# USBControlledAudioMixer.net
KiCad netlist of a schematic drawn in EAGLE
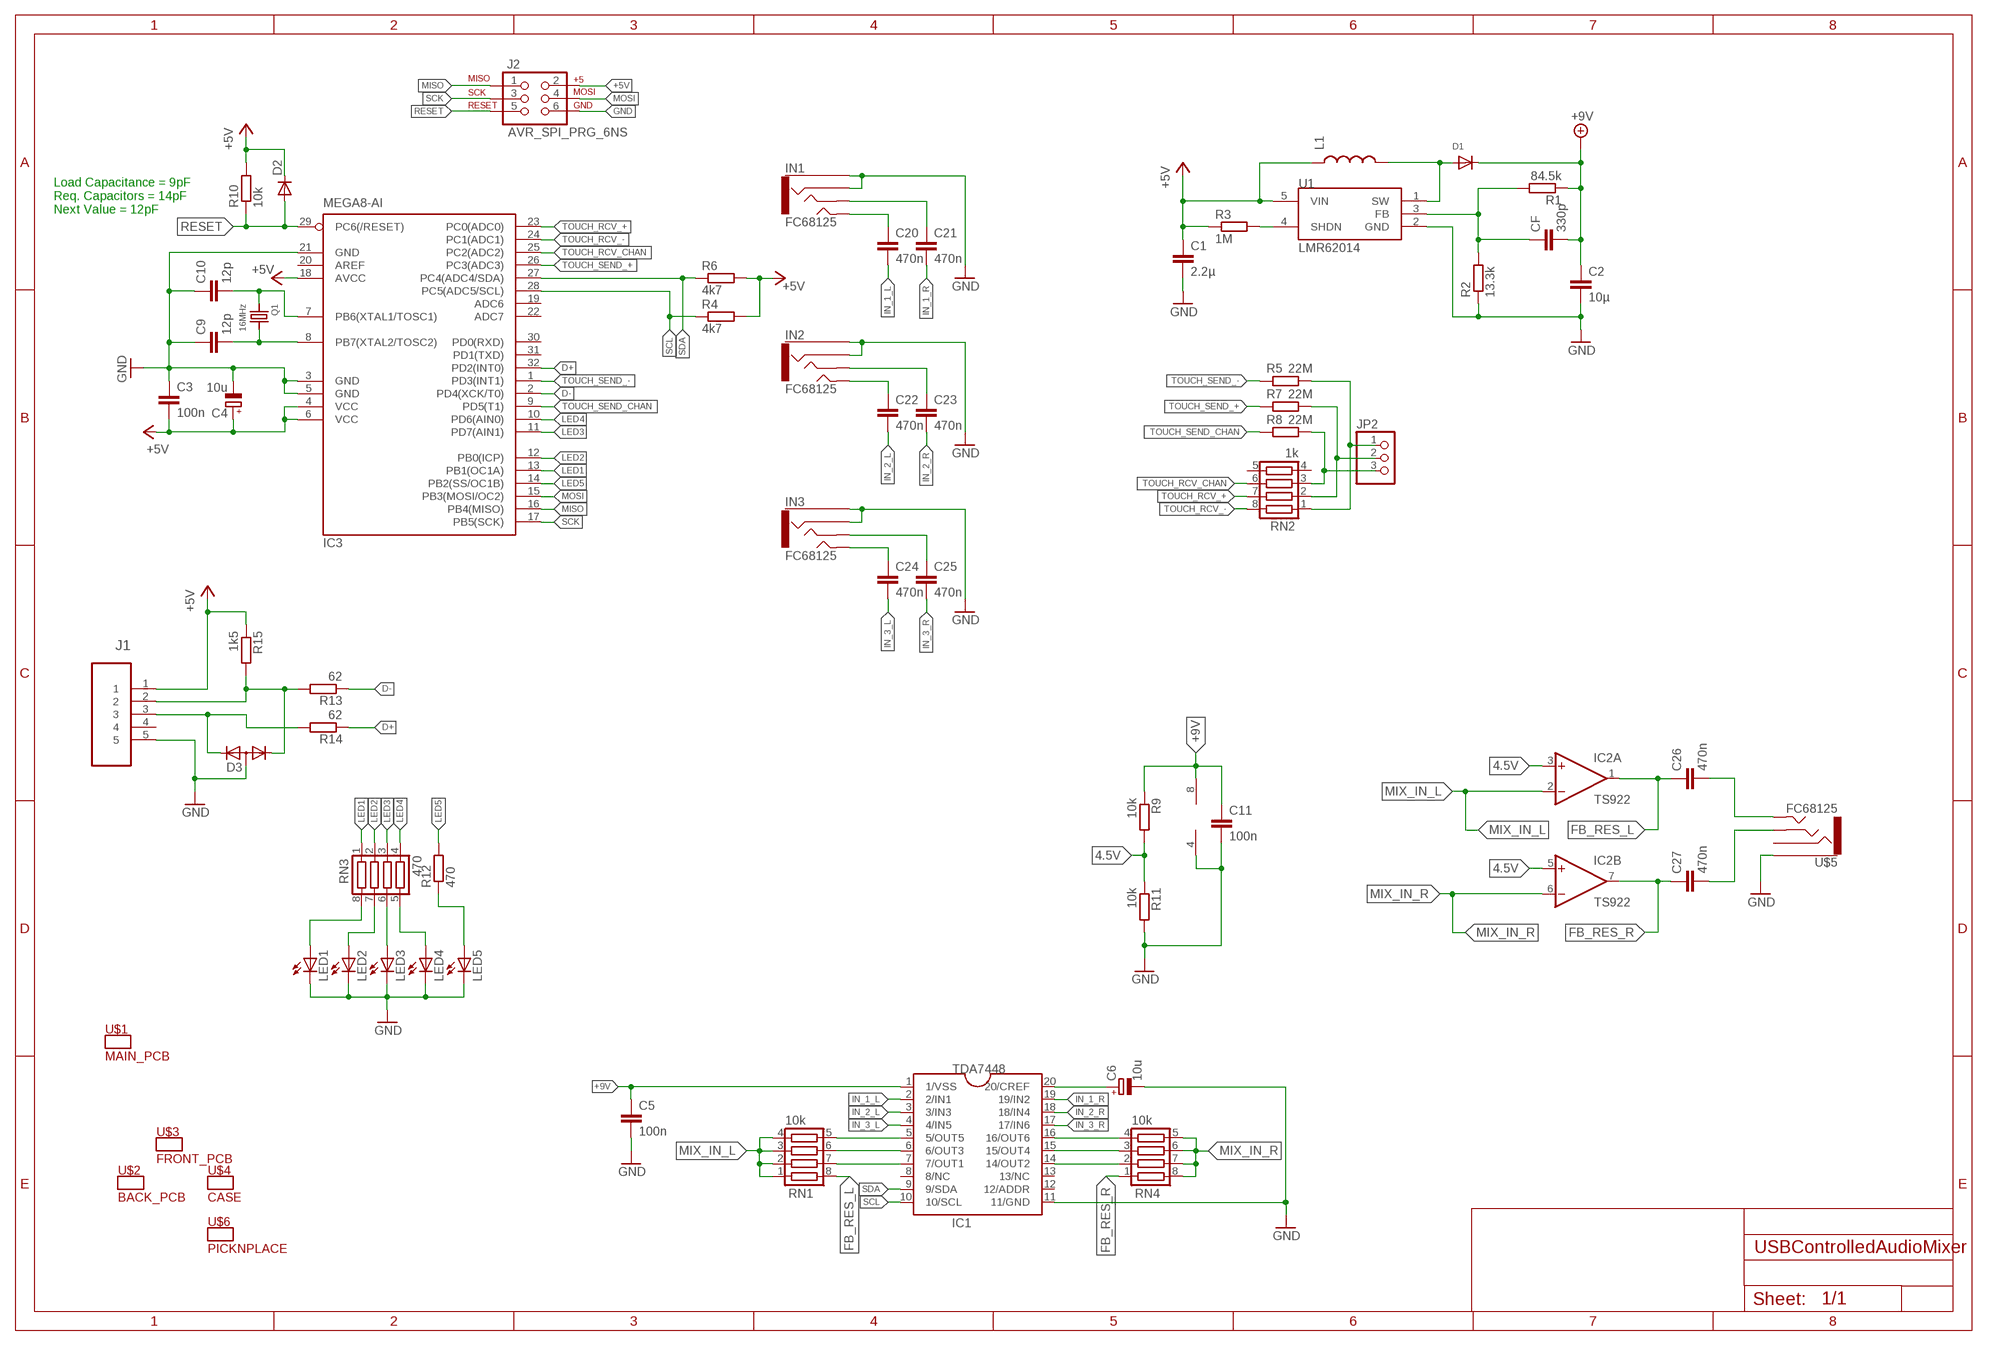
[diagram p0: schematic, sheet 1]

(export (version "E")
  (design (tool "Eeschema 10.0.6"))
  (components
    (comp (ref "C1")
      (value "2.2µ")
      (footprint "eagle-import:C0603")
      (libsource (lib "eagle-import") (part "C-EUC0603"))
    )
    (comp (ref "C2")
      (value "10µ")
      (footprint "eagle-import:C0805")
      (libsource (lib "eagle-import") (part "C-EUC0805"))
    )
    (comp (ref "C3")
      (value "100n")
      (footprint "eagle-import:C0603")
      (libsource (lib "eagle-import") (part "C-EUC0603"))
    )
    (comp (ref "C4")
      (value "10u")
      (footprint "eagle-import:SMC_A")
      (libsource (lib "eagle-import") (part "CPOL-EUSMCA"))
    )
    (comp (ref "C5")
      (value "100n")
      (footprint "eagle-import:C0603")
      (libsource (lib "eagle-import") (part "C-EUC0603"))
    )
    (comp (ref "C6")
      (value "10u")
      (footprint "eagle-import:SMC_A")
      (libsource (lib "eagle-import") (part "CPOL-EUSMCA"))
    )
    (comp (ref "C9")
      (value "12p")
      (footprint "eagle-import:C0603")
      (libsource (lib "eagle-import") (part "C-EUC0603"))
    )
    (comp (ref "C10")
      (value "12p")
      (footprint "eagle-import:C0603")
      (libsource (lib "eagle-import") (part "C-EUC0603"))
    )
    (comp (ref "C11")
      (value "100n")
      (footprint "eagle-import:C0603")
      (libsource (lib "eagle-import") (part "C-EUC0603"))
    )
    (comp (ref "C20")
      (value "470n")
      (footprint "eagle-import:C1206")
      (libsource (lib "eagle-import") (part "C-EUC1206"))
    )
    (comp (ref "C21")
      (value "470n")
      (footprint "eagle-import:C1206")
      (libsource (lib "eagle-import") (part "C-EUC1206"))
    )
    (comp (ref "C22")
      (value "470n")
      (footprint "eagle-import:C1206")
      (libsource (lib "eagle-import") (part "C-EUC1206"))
    )
    (comp (ref "C23")
      (value "470n")
      (footprint "eagle-import:C1206")
      (libsource (lib "eagle-import") (part "C-EUC1206"))
    )
    (comp (ref "C24")
      (value "470n")
      (footprint "eagle-import:C1206")
      (libsource (lib "eagle-import") (part "C-EUC1206"))
    )
    (comp (ref "C25")
      (value "470n")
      (footprint "eagle-import:C1206")
      (libsource (lib "eagle-import") (part "C-EUC1206"))
    )
    (comp (ref "C26")
      (value "470n")
      (footprint "eagle-import:C1206")
      (libsource (lib "eagle-import") (part "C-EUC1206"))
    )
    (comp (ref "C27")
      (value "470n")
      (footprint "eagle-import:C1206")
      (libsource (lib "eagle-import") (part "C-EUC1206"))
    )
    (comp (ref "CF")
      (value "330p")
      (footprint "eagle-import:C0603")
      (libsource (lib "eagle-import") (part "C-EUC0603"))
    )
    (comp (ref "D1")
      (value "DIODESOD-123")
      (footprint "eagle-import:SOD-123")
      (libsource (lib "eagle-import") (part "DIODESOD-123"))
    )
    (comp (ref "D2")
      (value "DIODE-SOD323-R")
      (footprint "eagle-import:SOD323-R")
      (libsource (lib "eagle-import") (part "DIODE-SOD323-R"))
    )
    (comp (ref "D3")
      (value "DIODE-2CA|ACSOT23")
      (footprint "eagle-import:SOT23")
      (libsource (lib "eagle-import") (part "DIODE-2CA|ACSOT23"))
    )
    (comp (ref "IC1")
      (value "TDA7448")
      (footprint "eagle-import:SO20")
      (libsource (lib "eagle-import") (part "TDA7448"))
    )
    (comp (ref "IC2")
      (value "TS922")
      (footprint "eagle-import:SO08")
      (fields (field (name "OC_DIGIKEY") "497-6035-1-ND") (field (name "PRICE_100") "0.546"))
      (libsource (lib "eagle-import") (part "LM358D"))
    )
    (comp (ref "IC3")
      (value "MEGA8-AI")
      (footprint "eagle-import:TQFP32-08")
      (fields (field (name "MPN") "ATMEGA8-16AU"))
      (libsource (lib "eagle-import") (part "MEGA8-AI"))
    )
    (comp (ref "IN1")
      (value "FC68125")
      (footprint "eagle-import:FC68125")
      (libsource (lib "eagle-import") (part "FC68125"))
    )
    (comp (ref "IN2")
      (value "FC68125")
      (footprint "eagle-import:FC68125")
      (libsource (lib "eagle-import") (part "FC68125"))
    )
    (comp (ref "IN3")
      (value "FC68125")
      (footprint "eagle-import:FC68125")
      (libsource (lib "eagle-import") (part "FC68125"))
    )
    (comp (ref "J1")
      (value "47346-0001")
      (footprint "eagle-import:MOLEX_47346-0001")
      (libsource (lib "eagle-import") (part "47346-0001"))
    )
    (comp (ref "J2")
      (value "AVR_SPI_PRG_6NS")
      (footprint "eagle-import:2X3-NS")
      (libsource (lib "eagle-import") (part "AVR_SPI_PRG_6NS"))
    )
    (comp (ref "JP2")
      (value "PINHD-1X3")
      (footprint "eagle-import:1X03_90_MOLEX_4094")
      (libsource (lib "eagle-import") (part "PINHD-1X3"))
    )
    (comp (ref "L1")
      (value "INDUCTOR1007")
      (footprint "eagle-import:1007")
      (libsource (lib "eagle-import") (part "INDUCTOR1007"))
    )
    (comp (ref "LED1")
      (value "LED0603")
      (footprint "eagle-import:LED-0603")
      (libsource (lib "eagle-import") (part "LED0603"))
    )
    (comp (ref "LED2")
      (value "LED0603")
      (footprint "eagle-import:LED-0603")
      (libsource (lib "eagle-import") (part "LED0603"))
    )
    (comp (ref "LED3")
      (value "LED0603")
      (footprint "eagle-import:LED-0603")
      (libsource (lib "eagle-import") (part "LED0603"))
    )
    (comp (ref "LED4")
      (value "LED0603")
      (footprint "eagle-import:LED-0603")
      (libsource (lib "eagle-import") (part "LED0603"))
    )
    (comp (ref "LED5")
      (value "LED0603")
      (footprint "eagle-import:LED-0603")
      (libsource (lib "eagle-import") (part "LED0603"))
    )
    (comp (ref "Q1")
      (value "16MHz")
      (footprint "eagle-import:CRYSTAL_3.2X2.5")
      (libsource (lib "eagle-import") (part "CRYSTALTHIN"))
    )
    (comp (ref "R1")
      (value "84.5k")
      (footprint "eagle-import:R0603")
      (libsource (lib "eagle-import") (part "R-EU_R0603"))
    )
    (comp (ref "R2")
      (value "13.3k")
      (footprint "eagle-import:R0603")
      (libsource (lib "eagle-import") (part "R-EU_R0603"))
    )
    (comp (ref "R3")
      (value "1M")
      (footprint "eagle-import:R0603")
      (libsource (lib "eagle-import") (part "R-EU_R0603"))
    )
    (comp (ref "R4")
      (value "4k7")
      (footprint "eagle-import:R0603")
      (libsource (lib "eagle-import") (part "R-EU_R0603"))
    )
    (comp (ref "R5")
      (value "22M")
      (footprint "eagle-import:R0603")
      (libsource (lib "eagle-import") (part "R-EU_R0603"))
    )
    (comp (ref "R6")
      (value "4k7")
      (footprint "eagle-import:R0603")
      (libsource (lib "eagle-import") (part "R-EU_R0603"))
    )
    (comp (ref "R7")
      (value "22M")
      (footprint "eagle-import:R0603")
      (libsource (lib "eagle-import") (part "R-EU_R0603"))
    )
    (comp (ref "R8")
      (value "22M")
      (footprint "eagle-import:R0603")
      (libsource (lib "eagle-import") (part "R-EU_R0603"))
    )
    (comp (ref "R9")
      (value "10k")
      (footprint "eagle-import:R0603")
      (libsource (lib "eagle-import") (part "R-EU_R0603"))
    )
    (comp (ref "R10")
      (value "10k")
      (footprint "eagle-import:R0603")
      (libsource (lib "eagle-import") (part "R-EU_R0603"))
    )
    (comp (ref "R11")
      (value "10k")
      (footprint "eagle-import:R0603")
      (libsource (lib "eagle-import") (part "R-EU_R0603"))
    )
    (comp (ref "R12")
      (value "470")
      (footprint "eagle-import:R0603")
      (libsource (lib "eagle-import") (part "R-EU_R0603"))
    )
    (comp (ref "R13")
      (value "62")
      (footprint "eagle-import:R0603")
      (libsource (lib "eagle-import") (part "R-EU_R0603"))
    )
    (comp (ref "R14")
      (value "62")
      (footprint "eagle-import:R0603")
      (libsource (lib "eagle-import") (part "R-EU_R0603"))
    )
    (comp (ref "R15")
      (value "1k5")
      (footprint "eagle-import:R0603")
      (libsource (lib "eagle-import") (part "R-EU_R0603"))
    )
    (comp (ref "RN1")
      (value "10k")
      (footprint "eagle-import:YC164")
      (libsource (lib "eagle-import") (part "RES_ARR"))
    )
    (comp (ref "RN2")
      (value "1k")
      (footprint "eagle-import:YC164")
      (libsource (lib "eagle-import") (part "RES_ARR"))
    )
    (comp (ref "RN3")
      (value "470")
      (footprint "eagle-import:YC164")
      (libsource (lib "eagle-import") (part "RES_ARR"))
    )
    (comp (ref "RN4")
      (value "10k")
      (footprint "eagle-import:YC164")
      (libsource (lib "eagle-import") (part "RES_ARR"))
    )
    (comp (ref "U$5")
      (value "FC68125")
      (footprint "eagle-import:FC68125")
      (libsource (lib "eagle-import") (part "FC68125"))
    )
    (comp (ref "U1")
      (value "LMR62014")
      (footprint "eagle-import:SOT-23")
      (libsource (lib "eagle-import") (part "LMR62014"))
    )
  )
  (nets
    (net (code "1") (name "+5V") (class "Default")
      (node (ref "C1") (pin "1") (pinfunction "1_1") (pintype "passive"))
      (node (ref "C3") (pin "2") (pinfunction "2_2") (pintype "passive"))
      (node (ref "C4") (pin "+") (pinfunction "+_+") (pintype "passive"))
      (node (ref "D2") (pin "C") (pinfunction "C_C") (pintype "passive"))
      (node (ref "IC3") (pin "18") (pinfunction "AVCC_18") (pintype "power_in"))
      (node (ref "IC3") (pin "4") (pinfunction "VCC_4") (pintype "power_in"))
      (node (ref "IC3") (pin "6") (pinfunction "VCC_6") (pintype "power_in"))
      (node (ref "J1") (pin "1") (pinfunction "1_1") (pintype "input"))
      (node (ref "J2") (pin "2") (pinfunction "2_2") (pintype "passive"))
      (node (ref "L1") (pin "1") (pinfunction "1_1") (pintype "passive"))
      (node (ref "R10") (pin "2") (pinfunction "2_2") (pintype "passive"))
      (node (ref "R15") (pin "1") (pinfunction "1_1") (pintype "passive"))
      (node (ref "R3") (pin "1") (pinfunction "1_1") (pintype "passive"))
      (node (ref "R4") (pin "2") (pinfunction "2_2") (pintype "passive"))
      (node (ref "R6") (pin "2") (pinfunction "2_2") (pintype "passive"))
      (node (ref "U1") (pin "5") (pinfunction "VIN_5") (pintype "power_in"))
    )
    (net (code "2") (name "+9V") (class "Default")
      (node (ref "C11") (pin "1") (pinfunction "1_1") (pintype "passive"))
      (node (ref "C2") (pin "1") (pinfunction "1_1") (pintype "passive"))
      (node (ref "C5") (pin "1") (pinfunction "1_1") (pintype "passive"))
      (node (ref "CF") (pin "2") (pinfunction "2_2") (pintype "passive"))
      (node (ref "D1") (pin "C") (pinfunction "C_C") (pintype "passive"))
      (node (ref "IC1") (pin "1") (pinfunction "1/VSS_1") (pintype "power_in"))
      (node (ref "IC2") (pin "8") (pinfunction "V+_8") (pintype "power_in"))
      (node (ref "R1") (pin "1") (pinfunction "1_1") (pintype "passive"))
      (node (ref "R9") (pin "1") (pinfunction "1_1") (pintype "passive"))
    )
    (net (code "3") (name "4.5V") (class "Default")
      (node (ref "IC2") (pin "3") (pinfunction "+IN_3") (pintype "input"))
      (node (ref "IC2") (pin "5") (pinfunction "+IN_5") (pintype "input"))
      (node (ref "R11") (pin "1") (pinfunction "1_1") (pintype "passive"))
      (node (ref "R9") (pin "2") (pinfunction "2_2") (pintype "passive"))
    )
    (net (code "4") (name "D+") (class "Default")
      (node (ref "IC3") (pin "32") (pinfunction "PD2(INT0)_32") (pintype "bidirectional"))
      (node (ref "R14") (pin "1") (pinfunction "1_1") (pintype "passive"))
    )
    (net (code "5") (name "D-") (class "Default")
      (node (ref "IC3") (pin "2") (pinfunction "PD4(XCK/T0)_2") (pintype "bidirectional"))
      (node (ref "R13") (pin "1") (pinfunction "1_1") (pintype "passive"))
    )
    (net (code "6") (name "FB_RES_L") (class "Default")
      (node (ref "C26") (pin "1") (pinfunction "1_1") (pintype "passive"))
      (node (ref "IC2") (pin "1") (pinfunction "OUT_1") (pintype "output"))
      (node (ref "RN1") (pin "8") (pinfunction "8_8") (pintype "passive"))
    )
    (net (code "7") (name "FB_RES_R") (class "Default")
      (node (ref "C27") (pin "1") (pinfunction "1_1") (pintype "passive"))
      (node (ref "IC2") (pin "7") (pinfunction "OUT_7") (pintype "output"))
      (node (ref "RN4") (pin "1") (pinfunction "1_1") (pintype "passive"))
    )
    (net (code "8") (name "GND") (class "Default")
      (node (ref "C1") (pin "2") (pinfunction "2_2") (pintype "passive"))
      (node (ref "C10") (pin "1") (pinfunction "1_1") (pintype "passive"))
      (node (ref "C11") (pin "2") (pinfunction "2_2") (pintype "passive"))
      (node (ref "C2") (pin "2") (pinfunction "2_2") (pintype "passive"))
      (node (ref "C3") (pin "1") (pinfunction "1_1") (pintype "passive"))
      (node (ref "C4") (pin "-") (pinfunction "-_-") (pintype "passive"))
      (node (ref "C5") (pin "2") (pinfunction "2_2") (pintype "passive"))
      (node (ref "C6") (pin "-") (pinfunction "-_-") (pintype "passive"))
      (node (ref "C9") (pin "1") (pinfunction "1_1") (pintype "passive"))
      (node (ref "D3") (pin "3") (pinfunction "A_3") (pintype "passive"))
      (node (ref "IC1") (pin "11") (pinfunction "11/GND_11") (pintype "power_in"))
      (node (ref "IC2") (pin "4") (pinfunction "V-_4") (pintype "power_in"))
      (node (ref "IC3") (pin "21") (pinfunction "GND_21") (pintype "power_in"))
      (node (ref "IC3") (pin "3") (pinfunction "GND_3") (pintype "power_in"))
      (node (ref "IC3") (pin "5") (pinfunction "GND_5") (pintype "power_in"))
      (node (ref "IN1") (pin "1") (pinfunction "1_1") (pintype "bidirectional"))
      (node (ref "IN1") (pin "6") (pinfunction "2_6") (pintype "bidirectional"))
      (node (ref "IN2") (pin "1") (pinfunction "1_1") (pintype "bidirectional"))
      (node (ref "IN2") (pin "6") (pinfunction "2_6") (pintype "bidirectional"))
      (node (ref "IN3") (pin "1") (pinfunction "1_1") (pintype "bidirectional"))
      (node (ref "IN3") (pin "6") (pinfunction "2_6") (pintype "bidirectional"))
      (node (ref "J1") (pin "5") (pinfunction "5_5") (pintype "input"))
      (node (ref "J2") (pin "6") (pinfunction "6_6") (pintype "passive"))
      (node (ref "LED1") (pin "C") (pinfunction "C_C") (pintype "passive"))
      (node (ref "LED2") (pin "C") (pinfunction "C_C") (pintype "passive"))
      (node (ref "LED3") (pin "C") (pinfunction "C_C") (pintype "passive"))
      (node (ref "LED4") (pin "C") (pinfunction "C_C") (pintype "passive"))
      (node (ref "LED5") (pin "C") (pinfunction "C_C") (pintype "passive"))
      (node (ref "R11") (pin "2") (pinfunction "2_2") (pintype "passive"))
      (node (ref "R2") (pin "1") (pinfunction "1_1") (pintype "passive"))
      (node (ref "U$5") (pin "1") (pinfunction "1_1") (pintype "bidirectional"))
      (node (ref "U1") (pin "2") (pinfunction "GND_2") (pintype "power_in"))
    )
    (net (code "9") (name "IN_1_L") (class "Default")
      (node (ref "C20") (pin "2") (pinfunction "2_2") (pintype "passive"))
      (node (ref "IC1") (pin "2") (pinfunction "2/IN1_2") (pintype "input"))
    )
    (net (code "10") (name "IN_1_R") (class "Default")
      (node (ref "C21") (pin "2") (pinfunction "2_2") (pintype "passive"))
      (node (ref "IC1") (pin "19") (pinfunction "19/IN2_19") (pintype "input"))
    )
    (net (code "11") (name "IN_2_L") (class "Default")
      (node (ref "C22") (pin "2") (pinfunction "2_2") (pintype "passive"))
      (node (ref "IC1") (pin "3") (pinfunction "3/IN3_3") (pintype "input"))
    )
    (net (code "12") (name "IN_2_R") (class "Default")
      (node (ref "C23") (pin "2") (pinfunction "2_2") (pintype "passive"))
      (node (ref "IC1") (pin "18") (pinfunction "18/IN4_18") (pintype "input"))
    )
    (net (code "13") (name "IN_3_L") (class "Default")
      (node (ref "C24") (pin "2") (pinfunction "2_2") (pintype "passive"))
      (node (ref "IC1") (pin "4") (pinfunction "4/IN5_4") (pintype "input"))
    )
    (net (code "14") (name "IN_3_R") (class "Default")
      (node (ref "C25") (pin "2") (pinfunction "2_2") (pintype "passive"))
      (node (ref "IC1") (pin "17") (pinfunction "17/IN6_17") (pintype "input"))
    )
    (net (code "15") (name "LED1") (class "Default")
      (node (ref "IC3") (pin "13") (pinfunction "PB1(OC1A)_13") (pintype "bidirectional"))
      (node (ref "RN3") (pin "1") (pinfunction "1_1") (pintype "passive"))
    )
    (net (code "16") (name "LED2") (class "Default")
      (node (ref "IC3") (pin "12") (pinfunction "PB0(ICP)_12") (pintype "bidirectional"))
      (node (ref "RN3") (pin "2") (pinfunction "2_2") (pintype "passive"))
    )
    (net (code "17") (name "LED3") (class "Default")
      (node (ref "IC3") (pin "11") (pinfunction "PD7(AIN1)_11") (pintype "bidirectional"))
      (node (ref "RN3") (pin "3") (pinfunction "3_3") (pintype "passive"))
    )
    (net (code "18") (name "LED4") (class "Default")
      (node (ref "IC3") (pin "10") (pinfunction "PD6(AIN0)_10") (pintype "bidirectional"))
      (node (ref "RN3") (pin "4") (pinfunction "4_4") (pintype "passive"))
    )
    (net (code "19") (name "LED5") (class "Default")
      (node (ref "IC3") (pin "14") (pinfunction "PB2(SS/OC1B)_14") (pintype "bidirectional"))
      (node (ref "R12") (pin "2") (pinfunction "2_2") (pintype "passive"))
    )
    (net (code "20") (name "MISO") (class "Default")
      (node (ref "IC3") (pin "16") (pinfunction "PB4(MISO)_16") (pintype "bidirectional"))
      (node (ref "J2") (pin "1") (pinfunction "1_1") (pintype "passive"))
    )
    (net (code "21") (name "MIX_IN_L") (class "Default")
      (node (ref "IC2") (pin "2") (pinfunction "-IN_2") (pintype "input"))
      (node (ref "RN1") (pin "1") (pinfunction "1_1") (pintype "passive"))
      (node (ref "RN1") (pin "2") (pinfunction "2_2") (pintype "passive"))
      (node (ref "RN1") (pin "3") (pinfunction "3_3") (pintype "passive"))
      (node (ref "RN1") (pin "4") (pinfunction "4_4") (pintype "passive"))
    )
    (net (code "22") (name "MIX_IN_R") (class "Default")
      (node (ref "IC2") (pin "6") (pinfunction "-IN_6") (pintype "input"))
      (node (ref "RN4") (pin "5") (pinfunction "5_5") (pintype "passive"))
      (node (ref "RN4") (pin "6") (pinfunction "6_6") (pintype "passive"))
      (node (ref "RN4") (pin "7") (pinfunction "7_7") (pintype "passive"))
      (node (ref "RN4") (pin "8") (pinfunction "8_8") (pintype "passive"))
    )
    (net (code "23") (name "MOSI") (class "Default")
      (node (ref "IC3") (pin "15") (pinfunction "PB3(MOSI/OC2)_15") (pintype "bidirectional"))
      (node (ref "J2") (pin "4") (pinfunction "4_4") (pintype "passive"))
    )
    (net (code "24") (name "Net-(C21-Pad1)") (class "Default")
      (node (ref "C21") (pin "1") (pinfunction "1_1") (pintype "passive"))
      (node (ref "IN1") (pin "3") (pinfunction "3_3") (pintype "bidirectional"))
      (node (ref "IN1") (pin "3A") (pinfunction "3_3A") (pintype "bidirectional"))
    )
    (net (code "25") (name "Net-(C23-Pad1)") (class "Default")
      (node (ref "C23") (pin "1") (pinfunction "1_1") (pintype "passive"))
      (node (ref "IN2") (pin "3") (pinfunction "3_3") (pintype "bidirectional"))
      (node (ref "IN2") (pin "3A") (pinfunction "3_3A") (pintype "bidirectional"))
    )
    (net (code "26") (name "Net-(C25-Pad1)") (class "Default")
      (node (ref "C25") (pin "1") (pinfunction "1_1") (pintype "passive"))
      (node (ref "IN3") (pin "3") (pinfunction "3_3") (pintype "bidirectional"))
      (node (ref "IN3") (pin "3A") (pinfunction "3_3A") (pintype "bidirectional"))
    )
    (net (code "27") (name "Net-(C27-Pad2)") (class "Default")
      (node (ref "C27") (pin "2") (pinfunction "2_2") (pintype "passive"))
      (node (ref "U$5") (pin "3") (pinfunction "3_3") (pintype "bidirectional"))
      (node (ref "U$5") (pin "3A") (pinfunction "3_3A") (pintype "bidirectional"))
    )
    (net (code "28") (name "Net-(D3-K1)") (class "Default")
      (node (ref "D3") (pin "1") (pinfunction "K1_1") (pintype "passive"))
      (node (ref "J1") (pin "2") (pinfunction "2_2") (pintype "input"))
      (node (ref "R13") (pin "2") (pinfunction "2_2") (pintype "passive"))
      (node (ref "R15") (pin "2") (pinfunction "2_2") (pintype "passive"))
    )
    (net (code "29") (name "Net-(D3-K2)") (class "Default")
      (node (ref "D3") (pin "2") (pinfunction "K2_2") (pintype "passive"))
      (node (ref "J1") (pin "3") (pinfunction "3_3") (pintype "input"))
      (node (ref "R14") (pin "2") (pinfunction "2_2") (pintype "passive"))
    )
    (net (code "30") (name "Net-(IC1-5{slash}OUT5)") (class "Default")
      (node (ref "IC1") (pin "5") (pinfunction "5/OUT5_5") (pintype "output"))
      (node (ref "RN1") (pin "5") (pinfunction "5_5") (pintype "passive"))
    )
    (net (code "31") (name "Net-(IC1-6{slash}OUT3)") (class "Default")
      (node (ref "IC1") (pin "6") (pinfunction "6/OUT3_6") (pintype "output"))
      (node (ref "RN1") (pin "6") (pinfunction "6_6") (pintype "passive"))
    )
    (net (code "32") (name "Net-(IC1-7{slash}OUT1)") (class "Default")
      (node (ref "IC1") (pin "7") (pinfunction "7/OUT1_7") (pintype "output"))
      (node (ref "RN1") (pin "7") (pinfunction "7_7") (pintype "passive"))
    )
    (net (code "33") (name "Net-(IC1-14{slash}OUT2)") (class "Default")
      (node (ref "IC1") (pin "14") (pinfunction "14/OUT2_14") (pintype "output"))
      (node (ref "RN4") (pin "2") (pinfunction "2_2") (pintype "passive"))
    )
    (net (code "34") (name "Net-(IC1-15{slash}OUT4)") (class "Default")
      (node (ref "IC1") (pin "15") (pinfunction "15/OUT4_15") (pintype "output"))
      (node (ref "RN4") (pin "3") (pinfunction "3_3") (pintype "passive"))
    )
    (net (code "35") (name "Net-(IC1-16{slash}OUT6)") (class "Default")
      (node (ref "IC1") (pin "16") (pinfunction "16/OUT6_16") (pintype "output"))
      (node (ref "RN4") (pin "4") (pinfunction "4_4") (pintype "passive"))
    )
    (net (code "36") (name "Net-(IC1-20{slash}CREF)") (class "Default")
      (node (ref "C6") (pin "+") (pinfunction "+_+") (pintype "passive"))
      (node (ref "IC1") (pin "20") (pinfunction "20/CREF_20") (pintype "bidirectional"))
    )
    (net (code "37") (name "Net-(IC3-PB6(XTAL1{slash}TOSC1))") (class "Default")
      (node (ref "C10") (pin "2") (pinfunction "2_2") (pintype "passive"))
      (node (ref "IC3") (pin "7") (pinfunction "PB6(XTAL1/TOSC1)_7") (pintype "bidirectional"))
      (node (ref "Q1") (pin "1") (pinfunction "1_1") (pintype "passive"))
    )
    (net (code "38") (name "Net-(IC3-PB7(XTAL2{slash}TOSC2))") (class "Default")
      (node (ref "C9") (pin "2") (pinfunction "2_2") (pintype "passive"))
      (node (ref "IC3") (pin "8") (pinfunction "PB7(XTAL2/TOSC2)_8") (pintype "bidirectional"))
      (node (ref "Q1") (pin "2") (pinfunction "2_2") (pintype "passive"))
    )
    (net (code "39") (name "Net-(IN1-4)") (class "Default")
      (node (ref "C20") (pin "1") (pinfunction "1_1") (pintype "passive"))
      (node (ref "IN1") (pin "2") (pinfunction "4_2") (pintype "bidirectional"))
    )
    (net (code "40") (name "Net-(IN2-4)") (class "Default")
      (node (ref "C22") (pin "1") (pinfunction "1_1") (pintype "passive"))
      (node (ref "IN2") (pin "2") (pinfunction "4_2") (pintype "bidirectional"))
    )
    (net (code "41") (name "Net-(IN3-4)") (class "Default")
      (node (ref "C24") (pin "1") (pinfunction "1_1") (pintype "passive"))
      (node (ref "IN3") (pin "2") (pinfunction "4_2") (pintype "bidirectional"))
    )
    (net (code "42") (name "Net-(JP2-Pad1)") (class "Default")
      (node (ref "JP2") (pin "1") (pinfunction "1_1") (pintype "passive"))
      (node (ref "R5") (pin "2") (pinfunction "2_2") (pintype "passive"))
      (node (ref "RN2") (pin "1") (pinfunction "1_1") (pintype "passive"))
    )
    (net (code "43") (name "Net-(JP2-Pad2)") (class "Default")
      (node (ref "JP2") (pin "2") (pinfunction "2_2") (pintype "passive"))
      (node (ref "R7") (pin "2") (pinfunction "2_2") (pintype "passive"))
      (node (ref "RN2") (pin "2") (pinfunction "2_2") (pintype "passive"))
    )
    (net (code "44") (name "Net-(JP2-Pad3)") (class "Default")
      (node (ref "JP2") (pin "3") (pinfunction "3_3") (pintype "passive"))
      (node (ref "R8") (pin "2") (pinfunction "2_2") (pintype "passive"))
      (node (ref "RN2") (pin "3") (pinfunction "3_3") (pintype "passive"))
    )
    (net (code "45") (name "Net-(LED1-PadA)") (class "Default")
      (node (ref "LED1") (pin "A") (pinfunction "A_A") (pintype "passive"))
      (node (ref "RN3") (pin "8") (pinfunction "8_8") (pintype "passive"))
    )
    (net (code "46") (name "Net-(LED2-PadA)") (class "Default")
      (node (ref "LED2") (pin "A") (pinfunction "A_A") (pintype "passive"))
      (node (ref "RN3") (pin "7") (pinfunction "7_7") (pintype "passive"))
    )
    (net (code "47") (name "Net-(LED3-PadA)") (class "Default")
      (node (ref "LED3") (pin "A") (pinfunction "A_A") (pintype "passive"))
      (node (ref "RN3") (pin "6") (pinfunction "6_6") (pintype "passive"))
    )
    (net (code "48") (name "Net-(LED4-PadA)") (class "Default")
      (node (ref "LED4") (pin "A") (pinfunction "A_A") (pintype "passive"))
      (node (ref "RN3") (pin "5") (pinfunction "5_5") (pintype "passive"))
    )
    (net (code "49") (name "Net-(LED5-PadA)") (class "Default")
      (node (ref "LED5") (pin "A") (pinfunction "A_A") (pintype "passive"))
      (node (ref "R12") (pin "1") (pinfunction "1_1") (pintype "passive"))
    )
    (net (code "50") (name "Net-(U$5-4)") (class "Default")
      (node (ref "C26") (pin "2") (pinfunction "2_2") (pintype "passive"))
      (node (ref "U$5") (pin "2") (pinfunction "4_2") (pintype "bidirectional"))
    )
    (net (code "51") (name "Net-(U1-FB)") (class "Default")
      (node (ref "CF") (pin "1") (pinfunction "1_1") (pintype "passive"))
      (node (ref "R1") (pin "2") (pinfunction "2_2") (pintype "passive"))
      (node (ref "R2") (pin "2") (pinfunction "2_2") (pintype "passive"))
      (node (ref "U1") (pin "3") (pinfunction "FB_3") (pintype "bidirectional"))
    )
    (net (code "52") (name "Net-(U1-SHDN)") (class "Default")
      (node (ref "R3") (pin "2") (pinfunction "2_2") (pintype "passive"))
      (node (ref "U1") (pin "4") (pinfunction "SHDN_4") (pintype "bidirectional"))
    )
    (net (code "53") (name "Net-(U1-SW)") (class "Default")
      (node (ref "D1") (pin "A") (pinfunction "A_A") (pintype "passive"))
      (node (ref "L1") (pin "2") (pinfunction "2_2") (pintype "passive"))
      (node (ref "U1") (pin "1") (pinfunction "SW_1") (pintype "power_in"))
    )
    (net (code "54") (name "RESET") (class "Default")
      (node (ref "D2") (pin "A") (pinfunction "A_A") (pintype "passive"))
      (node (ref "IC3") (pin "29") (pinfunction "PC6(/RESET)_29") (pintype "bidirectional"))
      (node (ref "J2") (pin "5") (pinfunction "5_5") (pintype "passive"))
      (node (ref "R10") (pin "1") (pinfunction "1_1") (pintype "passive"))
    )
    (net (code "55") (name "SCK") (class "Default")
      (node (ref "IC3") (pin "17") (pinfunction "PB5(SCK)_17") (pintype "bidirectional"))
      (node (ref "J2") (pin "3") (pinfunction "3_3") (pintype "passive"))
    )
    (net (code "56") (name "SCL") (class "Default")
      (node (ref "IC1") (pin "10") (pinfunction "10/SCL_10") (pintype "bidirectional"))
      (node (ref "IC3") (pin "28") (pinfunction "PC5(ADC5/SCL)_28") (pintype "bidirectional"))
      (node (ref "R4") (pin "1") (pinfunction "1_1") (pintype "passive"))
    )
    (net (code "57") (name "SDA") (class "Default")
      (node (ref "IC1") (pin "9") (pinfunction "9/SDA_9") (pintype "bidirectional"))
      (node (ref "IC3") (pin "27") (pinfunction "PC4(ADC4/SDA)_27") (pintype "bidirectional"))
      (node (ref "R6") (pin "1") (pinfunction "1_1") (pintype "passive"))
    )
    (net (code "58") (name "TOUCH_RCV_+") (class "Default")
      (node (ref "IC3") (pin "23") (pinfunction "PC0(ADC0)_23") (pintype "bidirectional"))
      (node (ref "RN2") (pin "7") (pinfunction "7_7") (pintype "passive"))
    )
    (net (code "59") (name "TOUCH_RCV_-") (class "Default")
      (node (ref "IC3") (pin "24") (pinfunction "PC1(ADC1)_24") (pintype "bidirectional"))
      (node (ref "RN2") (pin "8") (pinfunction "8_8") (pintype "passive"))
    )
    (net (code "60") (name "TOUCH_RCV_CHAN") (class "Default")
      (node (ref "IC3") (pin "25") (pinfunction "PC2(ADC2)_25") (pintype "bidirectional"))
      (node (ref "RN2") (pin "6") (pinfunction "6_6") (pintype "passive"))
    )
    (net (code "61") (name "TOUCH_SEND_+") (class "Default")
      (node (ref "IC3") (pin "26") (pinfunction "PC3(ADC3)_26") (pintype "bidirectional"))
      (node (ref "R7") (pin "1") (pinfunction "1_1") (pintype "passive"))
    )
    (net (code "62") (name "TOUCH_SEND_-") (class "Default")
      (node (ref "IC3") (pin "1") (pinfunction "PD3(INT1)_1") (pintype "bidirectional"))
      (node (ref "R5") (pin "1") (pinfunction "1_1") (pintype "passive"))
    )
    (net (code "63") (name "TOUCH_SEND_CHAN") (class "Default")
      (node (ref "IC3") (pin "9") (pinfunction "PD5(T1)_9") (pintype "bidirectional"))
      (node (ref "R8") (pin "1") (pinfunction "1_1") (pintype "passive"))
    )
    (net (code "64") (name "unconnected-(IC1-8{slash}NC-Pad8)") (class "Default")
      (node (ref "IC1") (pin "8") (pinfunction "8/NC_8") (pintype "no_connect"))
    )
    (net (code "65") (name "unconnected-(IC1-12{slash}ADDR-Pad12)") (class "Default")
      (node (ref "IC1") (pin "12") (pinfunction "12/ADDR_12") (pintype "bidirectional"))
    )
    (net (code "66") (name "unconnected-(IC1-13{slash}NC-Pad13)") (class "Default")
      (node (ref "IC1") (pin "13") (pinfunction "13/NC_13") (pintype "no_connect"))
    )
    (net (code "67") (name "unconnected-(IC3-ADC6-Pad19)") (class "Default")
      (node (ref "IC3") (pin "19") (pinfunction "ADC6_19") (pintype "bidirectional"))
    )
    (net (code "68") (name "unconnected-(IC3-ADC7-Pad22)") (class "Default")
      (node (ref "IC3") (pin "22") (pinfunction "ADC7_22") (pintype "bidirectional"))
    )
    (net (code "69") (name "unconnected-(IC3-AREF-Pad20)") (class "Default")
      (node (ref "IC3") (pin "20") (pinfunction "AREF_20") (pintype "passive"))
    )
    (net (code "70") (name "unconnected-(IC3-PD0(RXD)-Pad30)") (class "Default")
      (node (ref "IC3") (pin "30") (pinfunction "PD0(RXD)_30") (pintype "bidirectional"))
    )
    (net (code "71") (name "unconnected-(IC3-PD1(TXD)-Pad31)") (class "Default")
      (node (ref "IC3") (pin "31") (pinfunction "PD1(TXD)_31") (pintype "bidirectional"))
    )
    (net (code "72") (name "unconnected-(J1-Pad4)") (class "Default")
      (node (ref "J1") (pin "4") (pinfunction "4_4") (pintype "input"))
    )
    (net (code "73") (name "unconnected-(RN2-Pad4)") (class "Default")
      (node (ref "RN2") (pin "4") (pinfunction "4_4") (pintype "passive"))
    )
    (net (code "74") (name "unconnected-(RN2-Pad5)") (class "Default")
      (node (ref "RN2") (pin "5") (pinfunction "5_5") (pintype "passive"))
    )
    (net (code "75") (name "unconnected-(U$5-2-Pad6)") (class "Default")
      (node (ref "U$5") (pin "6") (pinfunction "2_6") (pintype "bidirectional"))
    )
  )
)
